# Mother_Board.net
KiCad netlist of a schematic drawn in EAGLE
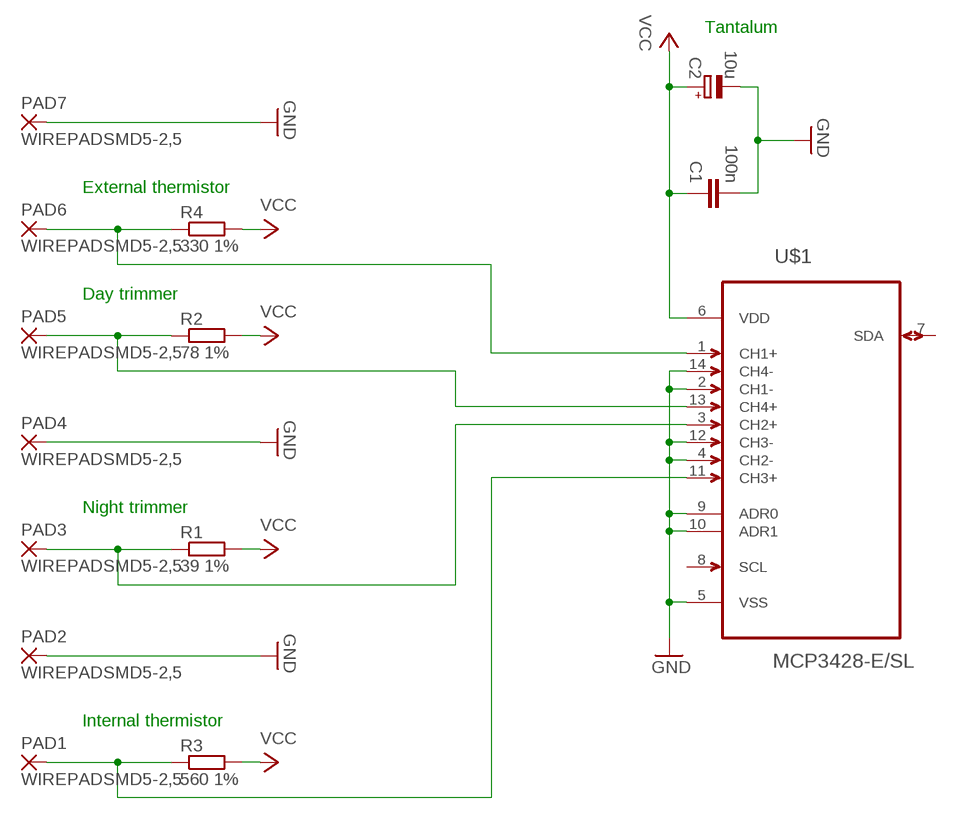
[diagram p0: schematic, sheet 1]

(export (version "E")
  (design (tool "Eeschema 10.0.6"))
  (components
    (comp (ref "C1")
      (value "100n")
      (footprint "eagle-import:C050-035X075")
      (libsource (lib "eagle-import") (part "C-EU050-035X075"))
    )
    (comp (ref "C2")
      (value "10u")
      (footprint "eagle-import:B45181B")
      (libsource (lib "eagle-import") (part "CPOL-EUB45181B"))
    )
    (comp (ref "PAD1")
      (value "WIREPADSMD5-2,5")
      (footprint "eagle-import:5-2,5")
      (libsource (lib "eagle-import") (part "WIREPADSMD5-2,5"))
    )
    (comp (ref "PAD2")
      (value "WIREPADSMD5-2,5")
      (footprint "eagle-import:5-2,5")
      (libsource (lib "eagle-import") (part "WIREPADSMD5-2,5"))
    )
    (comp (ref "PAD3")
      (value "WIREPADSMD5-2,5")
      (footprint "eagle-import:5-2,5")
      (libsource (lib "eagle-import") (part "WIREPADSMD5-2,5"))
    )
    (comp (ref "PAD4")
      (value "WIREPADSMD5-2,5")
      (footprint "eagle-import:5-2,5")
      (libsource (lib "eagle-import") (part "WIREPADSMD5-2,5"))
    )
    (comp (ref "PAD5")
      (value "WIREPADSMD5-2,5")
      (footprint "eagle-import:5-2,5")
      (libsource (lib "eagle-import") (part "WIREPADSMD5-2,5"))
    )
    (comp (ref "PAD6")
      (value "WIREPADSMD5-2,5")
      (footprint "eagle-import:5-2,5")
      (libsource (lib "eagle-import") (part "WIREPADSMD5-2,5"))
    )
    (comp (ref "PAD7")
      (value "WIREPADSMD5-2,5")
      (footprint "eagle-import:5-2,5")
      (libsource (lib "eagle-import") (part "WIREPADSMD5-2,5"))
    )
    (comp (ref "R1")
      (value "39 1%")
      (footprint "eagle-import:0207_10")
      (libsource (lib "eagle-import") (part "R-EU_0207/10"))
    )
    (comp (ref "R2")
      (value "78 1%")
      (footprint "eagle-import:0207_10")
      (libsource (lib "eagle-import") (part "R-EU_0207/10"))
    )
    (comp (ref "R3")
      (value "560 1%")
      (footprint "eagle-import:0207_10")
      (libsource (lib "eagle-import") (part "R-EU_0207/10"))
    )
    (comp (ref "R4")
      (value "330 1%")
      (footprint "eagle-import:0207_10")
      (libsource (lib "eagle-import") (part "R-EU_0207/10"))
    )
    (comp (ref "U$1")
      (value "MCP3428-E/SL")
      (footprint "eagle-import:SOIC127P600X175-14N")
      (libsource (lib "eagle-import") (part "MCP3428-E/SL"))
    )
  )
  (nets
    (net (code "1") (name "GND") (class "Default")
      (node (ref "C1") (pin "2") (pinfunction "2_2") (pintype "passive"))
      (node (ref "C2") (pin "-") (pinfunction "-_-") (pintype "passive"))
      (node (ref "PAD2") (pin "1") (pinfunction "P_1") (pintype "passive"))
      (node (ref "PAD4") (pin "1") (pinfunction "P_1") (pintype "passive"))
      (node (ref "PAD7") (pin "1") (pinfunction "P_1") (pintype "passive"))
      (node (ref "U$1") (pin "10") (pinfunction "ADR1_10") (pintype "passive"))
      (node (ref "U$1") (pin "12") (pinfunction "CH3-_12") (pintype "input"))
      (node (ref "U$1") (pin "14") (pinfunction "CH4-_14") (pintype "input"))
      (node (ref "U$1") (pin "2") (pinfunction "CH1-_2") (pintype "input"))
      (node (ref "U$1") (pin "4") (pinfunction "CH2-_4") (pintype "input"))
      (node (ref "U$1") (pin "5") (pinfunction "VSS_5") (pintype "power_in"))
      (node (ref "U$1") (pin "9") (pinfunction "ADR0_9") (pintype "passive"))
    )
    (net (code "2") (name "Net-(PAD1-P)") (class "Default")
      (node (ref "PAD1") (pin "1") (pinfunction "P_1") (pintype "passive"))
      (node (ref "R3") (pin "1") (pinfunction "1_1") (pintype "passive"))
      (node (ref "U$1") (pin "11") (pinfunction "CH3+_11") (pintype "input"))
    )
    (net (code "3") (name "Net-(PAD3-P)") (class "Default")
      (node (ref "PAD3") (pin "1") (pinfunction "P_1") (pintype "passive"))
      (node (ref "R1") (pin "1") (pinfunction "1_1") (pintype "passive"))
      (node (ref "U$1") (pin "3") (pinfunction "CH2+_3") (pintype "input"))
    )
    (net (code "4") (name "Net-(PAD5-P)") (class "Default")
      (node (ref "PAD5") (pin "1") (pinfunction "P_1") (pintype "passive"))
      (node (ref "R2") (pin "1") (pinfunction "1_1") (pintype "passive"))
      (node (ref "U$1") (pin "13") (pinfunction "CH4+_13") (pintype "input"))
    )
    (net (code "5") (name "Net-(PAD6-P)") (class "Default")
      (node (ref "PAD6") (pin "1") (pinfunction "P_1") (pintype "passive"))
      (node (ref "R4") (pin "1") (pinfunction "1_1") (pintype "passive"))
      (node (ref "U$1") (pin "1") (pinfunction "CH1+_1") (pintype "input"))
    )
    (net (code "6") (name "VCC") (class "Default")
      (node (ref "C1") (pin "1") (pinfunction "1_1") (pintype "passive"))
      (node (ref "C2") (pin "+") (pinfunction "+_+") (pintype "passive"))
      (node (ref "R1") (pin "2") (pinfunction "2_2") (pintype "passive"))
      (node (ref "R2") (pin "2") (pinfunction "2_2") (pintype "passive"))
      (node (ref "R3") (pin "2") (pinfunction "2_2") (pintype "passive"))
      (node (ref "R4") (pin "2") (pinfunction "2_2") (pintype "passive"))
      (node (ref "U$1") (pin "6") (pinfunction "VDD_6") (pintype "power_in"))
    )
    (net (code "7") (name "unconnected-(U$1-SCL-Pad8)") (class "Default")
      (node (ref "U$1") (pin "8") (pinfunction "SCL_8") (pintype "input"))
    )
    (net (code "8") (name "unconnected-(U$1-SDA-Pad7)") (class "Default")
      (node (ref "U$1") (pin "7") (pinfunction "SDA_7") (pintype "bidirectional"))
    )
  )
)
